# sd1.net
KiCad netlist of a schematic drawn in EAGLE
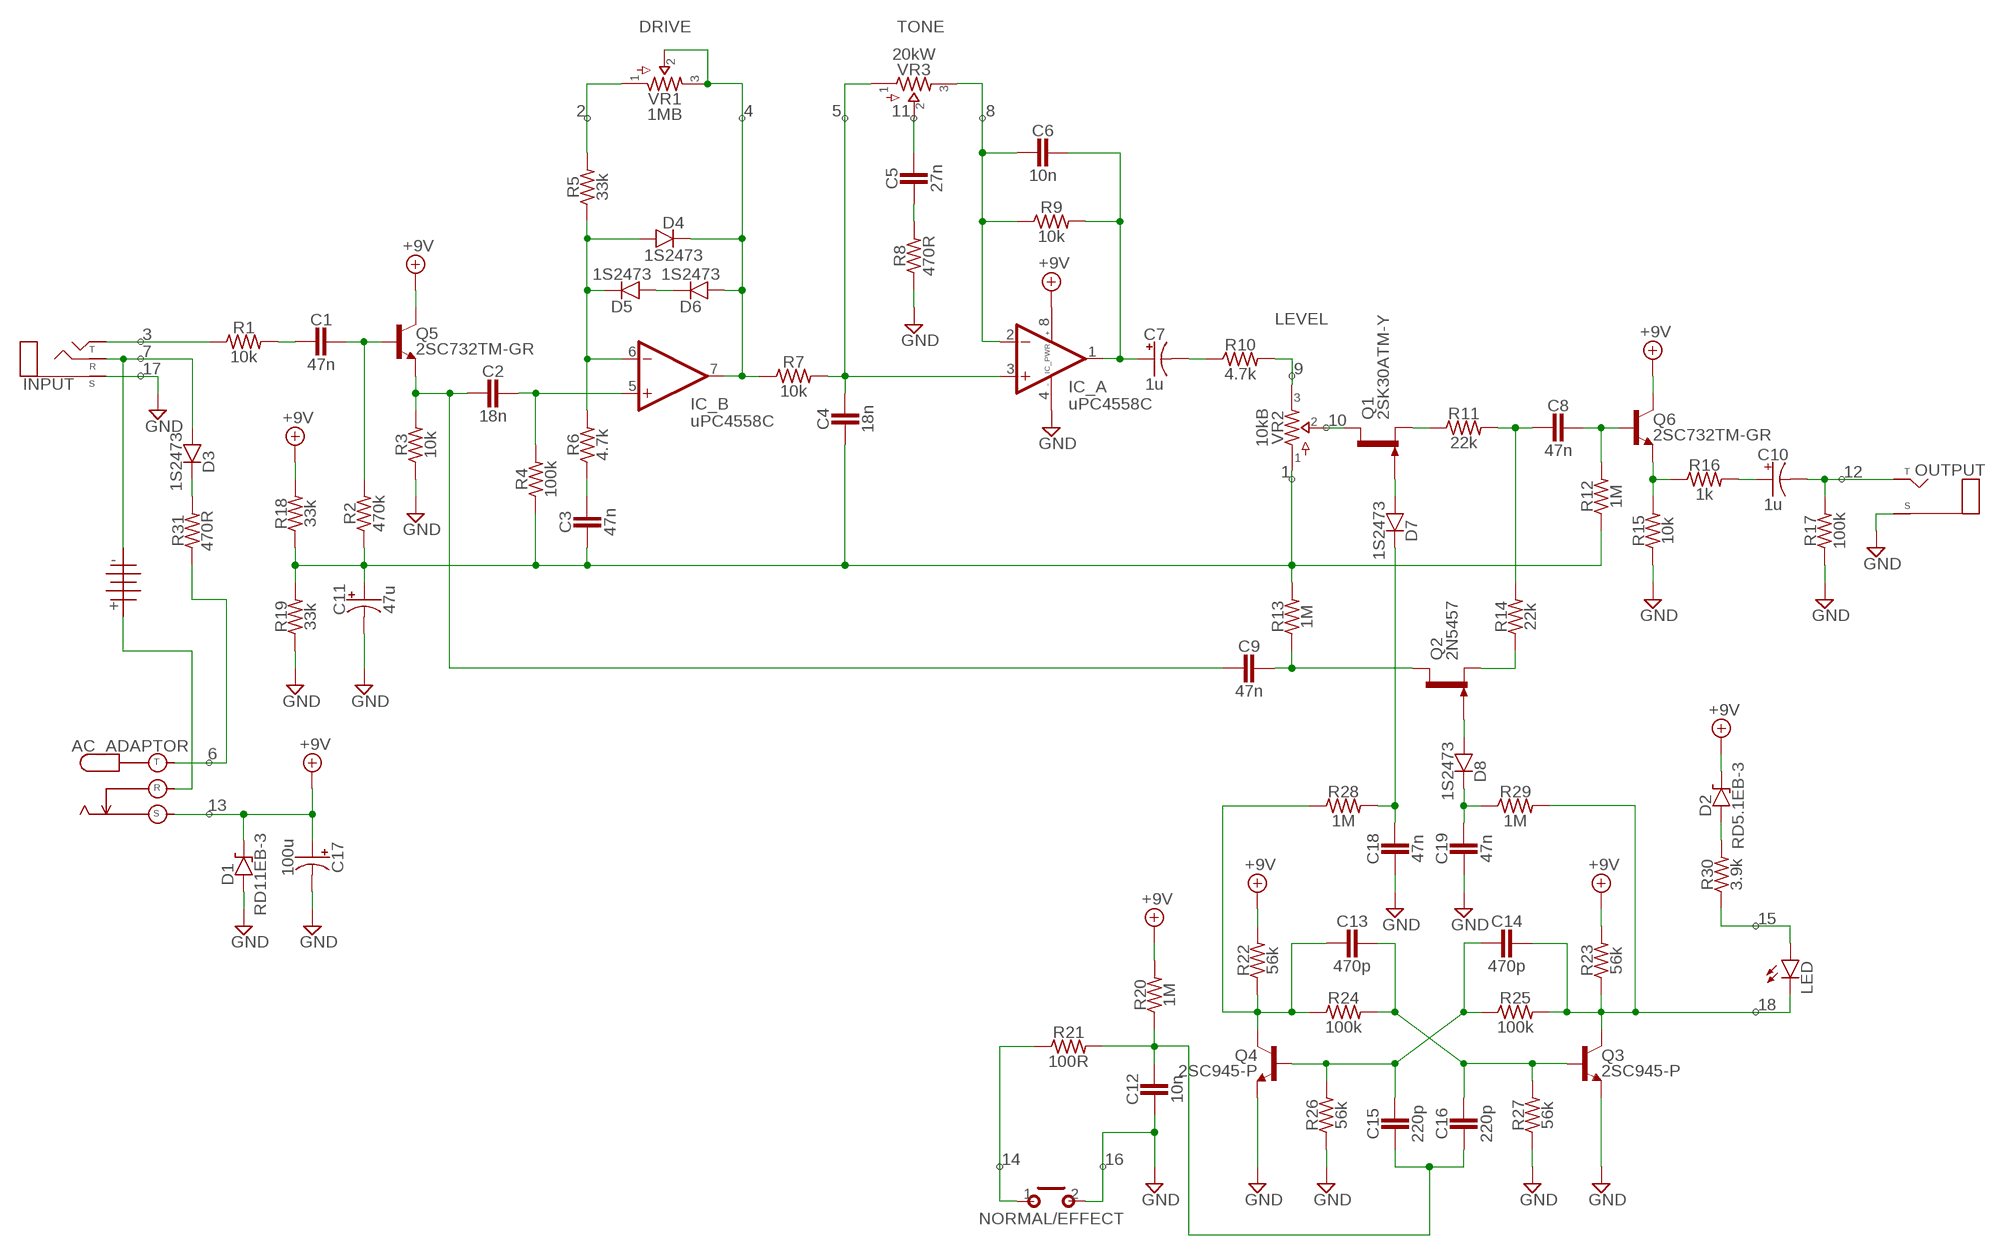
[diagram p0: schematic, sheet 1]

(export (version "E")
  (design (tool "Eeschema 10.0.6"))
  (components
    (comp (ref "AC_ADAPTOR")
      (value "DC_KOBICONN")
      (footprint "eagle-import:DC_KOBICONN")
      (libsource (lib "eagle-import") (part "DC_KOBICONN"))
    )
    (comp (ref "BATTERY")
      (value "BATTERY")
      (footprint "eagle-import:TWO_PADS")
      (libsource (lib "eagle-import") (part "BATTERY"))
    )
    (comp (ref "C1")
      (value "47n")
      (footprint "eagle-import:BOX_SMALL")
      (libsource (lib "eagle-import") (part "CER/FILMBOX.1"))
    )
    (comp (ref "C2")
      (value "18n")
      (footprint "eagle-import:BOX_SMALL")
      (libsource (lib "eagle-import") (part "CER/FILMBOX.1"))
    )
    (comp (ref "C3")
      (value "47n")
      (footprint "eagle-import:BOX_SMALL")
      (libsource (lib "eagle-import") (part "CER/FILMBOX.1"))
    )
    (comp (ref "C4")
      (value "18n")
      (footprint "eagle-import:BOX_SMALL")
      (libsource (lib "eagle-import") (part "CER/FILMBOX.1"))
    )
    (comp (ref "C5")
      (value "27n")
      (footprint "eagle-import:BOX_SMALL")
      (libsource (lib "eagle-import") (part "CER/FILMBOX.1"))
    )
    (comp (ref "C6")
      (value "10n")
      (footprint "eagle-import:BOX_SMALL")
      (libsource (lib "eagle-import") (part "CER/FILMBOX.1"))
    )
    (comp (ref "C7")
      (value "1u")
      (footprint "eagle-import:040_020")
      (libsource (lib "eagle-import") (part "0400"))
    )
    (comp (ref "C8")
      (value "47n")
      (footprint "eagle-import:BOX_SMALL")
      (libsource (lib "eagle-import") (part "CER/FILMBOX.1"))
    )
    (comp (ref "C9")
      (value "47n")
      (footprint "eagle-import:BOX_SMALL")
      (libsource (lib "eagle-import") (part "CER/FILMBOX.1"))
    )
    (comp (ref "C10")
      (value "1u")
      (footprint "eagle-import:040_020")
      (libsource (lib "eagle-import") (part "0400"))
    )
    (comp (ref "C11")
      (value "47u")
      (footprint "eagle-import:040_020")
      (libsource (lib "eagle-import") (part "0400"))
    )
    (comp (ref "C12")
      (value "10n")
      (footprint "eagle-import:BOX_SMALL")
      (libsource (lib "eagle-import") (part "CER/FILMBOX.1"))
    )
    (comp (ref "C13")
      (value "470p")
      (footprint "eagle-import:BOX_SMALL")
      (libsource (lib "eagle-import") (part "CER/FILMBOX.1"))
    )
    (comp (ref "C14")
      (value "470p")
      (footprint "eagle-import:BOX_SMALL")
      (libsource (lib "eagle-import") (part "CER/FILMBOX.1"))
    )
    (comp (ref "C15")
      (value "220p")
      (footprint "eagle-import:BOX_SMALL")
      (libsource (lib "eagle-import") (part "CER/FILMBOX.1"))
    )
    (comp (ref "C16")
      (value "220p")
      (footprint "eagle-import:BOX_SMALL")
      (libsource (lib "eagle-import") (part "CER/FILMBOX.1"))
    )
    (comp (ref "C17")
      (value "100u")
      (footprint "eagle-import:040_020")
      (libsource (lib "eagle-import") (part "0400"))
    )
    (comp (ref "C18")
      (value "47n")
      (footprint "eagle-import:BOX_SMALL")
      (libsource (lib "eagle-import") (part "CER/FILMBOX.1"))
    )
    (comp (ref "C19")
      (value "47n")
      (footprint "eagle-import:BOX_SMALL")
      (libsource (lib "eagle-import") (part "CER/FILMBOX.1"))
    )
    (comp (ref "D1")
      (value "RD11EB-3")
      (footprint "eagle-import:DO41-2")
      (libsource (lib "eagle-import") (part "ZENER.2"))
    )
    (comp (ref "D2")
      (value "RD5.1EB-3")
      (footprint "eagle-import:DO41-2")
      (libsource (lib "eagle-import") (part "ZENER.2"))
    )
    (comp (ref "D3")
      (value "1S2473")
      (footprint "eagle-import:DO35-2")
      (libsource (lib "eagle-import") (part "DO35.2"))
    )
    (comp (ref "D4")
      (value "1S2473")
      (footprint "eagle-import:DO35-2")
      (libsource (lib "eagle-import") (part "DO35.2"))
    )
    (comp (ref "D5")
      (value "1S2473")
      (footprint "eagle-import:DO35-2")
      (libsource (lib "eagle-import") (part "DO35.2"))
    )
    (comp (ref "D6")
      (value "1S2473")
      (footprint "eagle-import:DO35-2")
      (libsource (lib "eagle-import") (part "DO35.2"))
    )
    (comp (ref "D7")
      (value "1S2473")
      (footprint "eagle-import:DO35-2")
      (libsource (lib "eagle-import") (part "DO35.2"))
    )
    (comp (ref "D8")
      (value "1S2473")
      (footprint "eagle-import:DO35-2")
      (libsource (lib "eagle-import") (part "DO35.2"))
    )
    (comp (ref "IC")
      (value "uPC4558C")
      (footprint "eagle-import:DIL0")
      (libsource (lib "eagle-import") (part "DUALTH"))
    )
    (comp (ref "INPUT")
      (value "STEREO3PADS")
      (footprint "eagle-import:THREEPADS")
      (libsource (lib "eagle-import") (part "STEREO3PADS"))
    )
    (comp (ref "LED")
      (value "SLP1358")
      (footprint "eagle-import:3MM_D")
      (libsource (lib "eagle-import") (part "LED"))
    )
    (comp (ref "NORMAL/EFFECT")
      (value "MOMENTARY")
      (footprint "eagle-import:SPST")
      (libsource (lib "eagle-import") (part "MOMENTARY"))
    )
    (comp (ref "OUTPUT")
      (value "MONO")
      (footprint "eagle-import:TWO_PADS")
      (libsource (lib "eagle-import") (part "MONO"))
    )
    (comp (ref "Q1")
      (value "2SK30ATM-Y")
      (footprint "eagle-import:TO92-")
      (libsource (lib "eagle-import") (part "2N5457"))
    )
    (comp (ref "Q2")
      (value "2N5457")
      (footprint "eagle-import:TO92-")
      (libsource (lib "eagle-import") (part "2N5457"))
    )
    (comp (ref "Q3")
      (value "2SC945-P")
      (footprint "eagle-import:TO92-")
      (libsource (lib "eagle-import") (part "2SC828A"))
    )
    (comp (ref "Q4")
      (value "2SC945-P")
      (footprint "eagle-import:TO92-")
      (libsource (lib "eagle-import") (part "2SC828A"))
    )
    (comp (ref "Q5")
      (value "2SC732TM-GR")
      (footprint "eagle-import:TO92-")
      (libsource (lib "eagle-import") (part "2SC828A"))
    )
    (comp (ref "Q6")
      (value "2SC732TM-GR")
      (footprint "eagle-import:TO92-")
      (libsource (lib "eagle-import") (part "2SC828A"))
    )
    (comp (ref "R1")
      (value "10k")
      (footprint "eagle-import:R0207_3")
      (libsource (lib "eagle-import") (part "R_.3B"))
    )
    (comp (ref "R2")
      (value "470k")
      (footprint "eagle-import:R0207_3")
      (libsource (lib "eagle-import") (part "R_.3B"))
    )
    (comp (ref "R3")
      (value "10k")
      (footprint "eagle-import:R0207_3")
      (libsource (lib "eagle-import") (part "R_.3B"))
    )
    (comp (ref "R4")
      (value "100k")
      (footprint "eagle-import:R0207_3")
      (libsource (lib "eagle-import") (part "R_.3B"))
    )
    (comp (ref "R5")
      (value "33k")
      (footprint "eagle-import:R0207_3")
      (libsource (lib "eagle-import") (part "R_.3B"))
    )
    (comp (ref "R6")
      (value "4.7k")
      (footprint "eagle-import:R0207_3")
      (libsource (lib "eagle-import") (part "R_.3B"))
    )
    (comp (ref "R7")
      (value "10k")
      (footprint "eagle-import:R0207_3")
      (libsource (lib "eagle-import") (part "R_.3B"))
    )
    (comp (ref "R8")
      (value "470R")
      (footprint "eagle-import:R0207_3")
      (libsource (lib "eagle-import") (part "R_.3B"))
    )
    (comp (ref "R9")
      (value "10k")
      (footprint "eagle-import:R0207_3")
      (libsource (lib "eagle-import") (part "R_.3B"))
    )
    (comp (ref "R10")
      (value "4.7k")
      (footprint "eagle-import:R0207_3")
      (libsource (lib "eagle-import") (part "R_.3B"))
    )
    (comp (ref "R11")
      (value "22k")
      (footprint "eagle-import:R0207_3")
      (libsource (lib "eagle-import") (part "R_.3B"))
    )
    (comp (ref "R12")
      (value "1M")
      (footprint "eagle-import:R0207_3")
      (libsource (lib "eagle-import") (part "R_.3B"))
    )
    (comp (ref "R13")
      (value "1M")
      (footprint "eagle-import:R0207_3")
      (libsource (lib "eagle-import") (part "R_.3B"))
    )
    (comp (ref "R14")
      (value "22k")
      (footprint "eagle-import:R0207_3")
      (libsource (lib "eagle-import") (part "R_.3B"))
    )
    (comp (ref "R15")
      (value "10k")
      (footprint "eagle-import:R0207_3")
      (libsource (lib "eagle-import") (part "R_.3B"))
    )
    (comp (ref "R16")
      (value "1k")
      (footprint "eagle-import:R0207_3")
      (libsource (lib "eagle-import") (part "R_.3B"))
    )
    (comp (ref "R17")
      (value "100k")
      (footprint "eagle-import:R0207_3")
      (libsource (lib "eagle-import") (part "R_.3B"))
    )
    (comp (ref "R18")
      (value "33k")
      (footprint "eagle-import:R0207_3")
      (libsource (lib "eagle-import") (part "R_.3B"))
    )
    (comp (ref "R19")
      (value "33k")
      (footprint "eagle-import:R0207_3")
      (libsource (lib "eagle-import") (part "R_.3B"))
    )
    (comp (ref "R20")
      (value "1M")
      (footprint "eagle-import:R0207_3")
      (libsource (lib "eagle-import") (part "R_.3B"))
    )
    (comp (ref "R21")
      (value "100R")
      (footprint "eagle-import:R0207_3")
      (libsource (lib "eagle-import") (part "R_.3B"))
    )
    (comp (ref "R22")
      (value "56k")
      (footprint "eagle-import:R0207_3")
      (libsource (lib "eagle-import") (part "R_.3B"))
    )
    (comp (ref "R23")
      (value "56k")
      (footprint "eagle-import:R0207_3")
      (libsource (lib "eagle-import") (part "R_.3B"))
    )
    (comp (ref "R24")
      (value "100k")
      (footprint "eagle-import:R0207_3")
      (libsource (lib "eagle-import") (part "R_.3B"))
    )
    (comp (ref "R25")
      (value "100k")
      (footprint "eagle-import:R0207_3")
      (libsource (lib "eagle-import") (part "R_.3B"))
    )
    (comp (ref "R26")
      (value "56k")
      (footprint "eagle-import:R0207_3")
      (libsource (lib "eagle-import") (part "R_.3B"))
    )
    (comp (ref "R27")
      (value "56k")
      (footprint "eagle-import:R0207_3")
      (libsource (lib "eagle-import") (part "R_.3B"))
    )
    (comp (ref "R28")
      (value "1M")
      (footprint "eagle-import:R0207_3")
      (libsource (lib "eagle-import") (part "R_.3B"))
    )
    (comp (ref "R29")
      (value "1M")
      (footprint "eagle-import:R0207_3")
      (libsource (lib "eagle-import") (part "R_.3B"))
    )
    (comp (ref "R30")
      (value "3.9k")
      (footprint "eagle-import:R0207_3")
      (libsource (lib "eagle-import") (part "R_.3B"))
    )
    (comp (ref "R31")
      (value "470R")
      (footprint "eagle-import:R0207_3")
      (libsource (lib "eagle-import") (part "R_.3B"))
    )
    (comp (ref "VR1")
      (value "1MB")
      (footprint "eagle-import:16MM")
      (libsource (lib "eagle-import") (part "POTS16MM"))
    )
    (comp (ref "VR2")
      (value "10kB")
      (footprint "eagle-import:16MM")
      (libsource (lib "eagle-import") (part "POTS16MM"))
    )
    (comp (ref "VR3")
      (value "20kW")
      (footprint "eagle-import:16MM")
      (libsource (lib "eagle-import") (part "POTS16MM"))
    )
  )
  (nets
    (net (code "1") (name "+9V") (class "Default")
      (node (ref "AC_ADAPTOR") (pin "S") (pinfunction "S_S") (pintype "bidirectional"))
      (node (ref "C17") (pin "+") (pinfunction "+_+") (pintype "passive"))
      (node (ref "D1") (pin "C") (pinfunction "C_C") (pintype "passive"))
      (node (ref "D2") (pin "C") (pinfunction "C_C") (pintype "passive"))
      (node (ref "IC") (pin "8") (pinfunction "V+_8") (pintype "power_in"))
      (node (ref "Q5") (pin "2") (pinfunction "C_2") (pintype "passive"))
      (node (ref "Q6") (pin "2") (pinfunction "C_2") (pintype "passive"))
      (node (ref "R18") (pin "2") (pinfunction "2_2") (pintype "passive"))
      (node (ref "R20") (pin "2") (pinfunction "2_2") (pintype "passive"))
      (node (ref "R22") (pin "2") (pinfunction "2_2") (pintype "passive"))
      (node (ref "R23") (pin "2") (pinfunction "2_2") (pintype "passive"))
    )
    (net (code "2") (name "GND") (class "Default")
      (node (ref "C11") (pin "-") (pinfunction "-_-") (pintype "passive"))
      (node (ref "C12") (pin "2") (pinfunction "2_2") (pintype "passive"))
      (node (ref "C17") (pin "-") (pinfunction "-_-") (pintype "passive"))
      (node (ref "C18") (pin "2") (pinfunction "2_2") (pintype "passive"))
      (node (ref "C19") (pin "2") (pinfunction "2_2") (pintype "passive"))
      (node (ref "D1") (pin "A") (pinfunction "A_A") (pintype "passive"))
      (node (ref "IC") (pin "4") (pinfunction "V-_4") (pintype "power_in"))
      (node (ref "INPUT") (pin "SLEEVE") (pinfunction "S_SLEEVE") (pintype "passive"))
      (node (ref "NORMAL/EFFECT") (pin "2") (pinfunction "S_2") (pintype "passive"))
      (node (ref "OUTPUT") (pin "S") (pinfunction "SLEEVE_S") (pintype "passive"))
      (node (ref "Q3") (pin "3") (pinfunction "E_3") (pintype "passive"))
      (node (ref "Q4") (pin "3") (pinfunction "E_3") (pintype "passive"))
      (node (ref "R15") (pin "1") (pinfunction "1_1") (pintype "passive"))
      (node (ref "R17") (pin "1") (pinfunction "1_1") (pintype "passive"))
      (node (ref "R19") (pin "1") (pinfunction "1_1") (pintype "passive"))
      (node (ref "R26") (pin "1") (pinfunction "1_1") (pintype "passive"))
      (node (ref "R27") (pin "1") (pinfunction "1_1") (pintype "passive"))
      (node (ref "R3") (pin "1") (pinfunction "1_1") (pintype "passive"))
      (node (ref "R8") (pin "1") (pinfunction "1_1") (pintype "passive"))
    )
    (net (code "3") (name "Net-(AC_ADAPTOR-PadT)") (class "Default")
      (node (ref "AC_ADAPTOR") (pin "T") (pinfunction "T_T") (pintype "bidirectional"))
      (node (ref "R31") (pin "1") (pinfunction "1_1") (pintype "passive"))
    )
    (net (code "4") (name "Net-(BATTERY-P$1)") (class "Default")
      (node (ref "AC_ADAPTOR") (pin "R") (pinfunction "R_R") (pintype "bidirectional"))
      (node (ref "BATTERY") (pin "T") (pinfunction "P$1_T") (pintype "bidirectional"))
    )
    (net (code "5") (name "Net-(BATTERY-P$2)") (class "Default")
      (node (ref "BATTERY") (pin "S") (pinfunction "P$2_S") (pintype "bidirectional"))
      (node (ref "D3") (pin "A") (pinfunction "A_A") (pintype "passive"))
      (node (ref "INPUT") (pin "RING") (pinfunction "R_RING") (pintype "passive"))
    )
    (net (code "6") (name "Net-(C1-Pad2)") (class "Default")
      (node (ref "C1") (pin "2") (pinfunction "2_2") (pintype "passive"))
      (node (ref "R1") (pin "2") (pinfunction "2_2") (pintype "passive"))
    )
    (net (code "7") (name "Net-(C3-Pad1)") (class "Default")
      (node (ref "C3") (pin "1") (pinfunction "1_1") (pintype "passive"))
      (node (ref "R6") (pin "1") (pinfunction "1_1") (pintype "passive"))
    )
    (net (code "8") (name "Net-(C5-Pad1)") (class "Default")
      (node (ref "C5") (pin "1") (pinfunction "1_1") (pintype "passive"))
      (node (ref "VR3") (pin "2") (pinfunction "2_2") (pintype "passive"))
    )
    (net (code "9") (name "Net-(C5-Pad2)") (class "Default")
      (node (ref "C5") (pin "2") (pinfunction "2_2") (pintype "passive"))
      (node (ref "R8") (pin "2") (pinfunction "2_2") (pintype "passive"))
    )
    (net (code "10") (name "Net-(C7-Pad-)") (class "Default")
      (node (ref "C7") (pin "-") (pinfunction "-_-") (pintype "passive"))
      (node (ref "R10") (pin "1") (pinfunction "1_1") (pintype "passive"))
    )
    (net (code "11") (name "Net-(C8-Pad2)") (class "Default")
      (node (ref "C8") (pin "2") (pinfunction "2_2") (pintype "passive"))
      (node (ref "R11") (pin "2") (pinfunction "2_2") (pintype "passive"))
      (node (ref "R14") (pin "2") (pinfunction "2_2") (pintype "passive"))
    )
    (net (code "12") (name "Net-(C10-Pad+)") (class "Default")
      (node (ref "C10") (pin "+") (pinfunction "+_+") (pintype "passive"))
      (node (ref "R16") (pin "2") (pinfunction "2_2") (pintype "passive"))
    )
    (net (code "13") (name "Net-(C11-Pad+)") (class "Default")
      (node (ref "C11") (pin "+") (pinfunction "+_+") (pintype "passive"))
      (node (ref "C3") (pin "2") (pinfunction "2_2") (pintype "passive"))
      (node (ref "C4") (pin "2") (pinfunction "2_2") (pintype "passive"))
      (node (ref "R12") (pin "1") (pinfunction "1_1") (pintype "passive"))
      (node (ref "R13") (pin "2") (pinfunction "2_2") (pintype "passive"))
      (node (ref "R18") (pin "1") (pinfunction "1_1") (pintype "passive"))
      (node (ref "R19") (pin "2") (pinfunction "2_2") (pintype "passive"))
      (node (ref "R2") (pin "1") (pinfunction "1_1") (pintype "passive"))
      (node (ref "R4") (pin "1") (pinfunction "1_1") (pintype "passive"))
      (node (ref "VR2") (pin "1") (pinfunction "1_1") (pintype "passive"))
    )
    (net (code "14") (name "Net-(C12-Pad1)") (class "Default")
      (node (ref "C12") (pin "1") (pinfunction "1_1") (pintype "passive"))
      (node (ref "C15") (pin "2") (pinfunction "2_2") (pintype "passive"))
      (node (ref "C16") (pin "2") (pinfunction "2_2") (pintype "passive"))
      (node (ref "R20") (pin "1") (pinfunction "1_1") (pintype "passive"))
      (node (ref "R21") (pin "2") (pinfunction "2_2") (pintype "passive"))
    )
    (net (code "15") (name "Net-(C18-Pad1)") (class "Default")
      (node (ref "C18") (pin "1") (pinfunction "1_1") (pintype "passive"))
      (node (ref "D7") (pin "C") (pinfunction "C_C") (pintype "passive"))
      (node (ref "R28") (pin "2") (pinfunction "2_2") (pintype "passive"))
    )
    (net (code "16") (name "Net-(C19-Pad1)") (class "Default")
      (node (ref "C19") (pin "1") (pinfunction "1_1") (pintype "passive"))
      (node (ref "D8") (pin "C") (pinfunction "C_C") (pintype "passive"))
      (node (ref "R29") (pin "1") (pinfunction "1_1") (pintype "passive"))
    )
    (net (code "17") (name "Net-(D2-PadA)") (class "Default")
      (node (ref "D2") (pin "A") (pinfunction "A_A") (pintype "passive"))
      (node (ref "R30") (pin "2") (pinfunction "2_2") (pintype "passive"))
    )
    (net (code "18") (name "Net-(D3-PadC)") (class "Default")
      (node (ref "D3") (pin "C") (pinfunction "C_C") (pintype "passive"))
      (node (ref "R31") (pin "2") (pinfunction "2_2") (pintype "passive"))
    )
    (net (code "19") (name "Net-(D5-PadA)") (class "Default")
      (node (ref "D5") (pin "A") (pinfunction "A_A") (pintype "passive"))
      (node (ref "D6") (pin "C") (pinfunction "C_C") (pintype "passive"))
    )
    (net (code "20") (name "Net-(ICA-+IN)") (class "Default")
      (node (ref "C4") (pin "1") (pinfunction "1_1") (pintype "passive"))
      (node (ref "IC") (pin "3") (pinfunction "+IN_3") (pintype "input"))
      (node (ref "R7") (pin "2") (pinfunction "2_2") (pintype "passive"))
      (node (ref "VR3") (pin "1") (pinfunction "1_1") (pintype "passive"))
    )
    (net (code "21") (name "Net-(ICA--IN)") (class "Default")
      (node (ref "C6") (pin "2") (pinfunction "2_2") (pintype "passive"))
      (node (ref "IC") (pin "2") (pinfunction "-IN_2") (pintype "input"))
      (node (ref "R9") (pin "1") (pinfunction "1_1") (pintype "passive"))
      (node (ref "VR3") (pin "3") (pinfunction "3_3") (pintype "passive"))
    )
    (net (code "22") (name "Net-(ICA-OUT)") (class "Default")
      (node (ref "C6") (pin "1") (pinfunction "1_1") (pintype "passive"))
      (node (ref "C7") (pin "+") (pinfunction "+_+") (pintype "passive"))
      (node (ref "IC") (pin "1") (pinfunction "OUT_1") (pintype "output"))
      (node (ref "R9") (pin "2") (pinfunction "2_2") (pintype "passive"))
    )
    (net (code "23") (name "Net-(ICB-+IN)") (class "Default")
      (node (ref "C2") (pin "1") (pinfunction "1_1") (pintype "passive"))
      (node (ref "IC") (pin "5") (pinfunction "+IN_5") (pintype "input"))
      (node (ref "R4") (pin "2") (pinfunction "2_2") (pintype "passive"))
    )
    (net (code "24") (name "Net-(ICB--IN)") (class "Default")
      (node (ref "D4") (pin "A") (pinfunction "A_A") (pintype "passive"))
      (node (ref "D5") (pin "C") (pinfunction "C_C") (pintype "passive"))
      (node (ref "IC") (pin "6") (pinfunction "-IN_6") (pintype "input"))
      (node (ref "R5") (pin "1") (pinfunction "1_1") (pintype "passive"))
      (node (ref "R6") (pin "2") (pinfunction "2_2") (pintype "passive"))
    )
    (net (code "25") (name "Net-(ICB-OUT)") (class "Default")
      (node (ref "D4") (pin "C") (pinfunction "C_C") (pintype "passive"))
      (node (ref "D6") (pin "A") (pinfunction "A_A") (pintype "passive"))
      (node (ref "IC") (pin "7") (pinfunction "OUT_7") (pintype "output"))
      (node (ref "R7") (pin "1") (pinfunction "1_1") (pintype "passive"))
      (node (ref "VR1") (pin "2") (pinfunction "2_2") (pintype "passive"))
      (node (ref "VR1") (pin "3") (pinfunction "3_3") (pintype "passive"))
    )
    (net (code "26") (name "Net-(INPUT-T)") (class "Default")
      (node (ref "INPUT") (pin "TIP") (pinfunction "T_TIP") (pintype "passive"))
      (node (ref "R1") (pin "1") (pinfunction "1_1") (pintype "passive"))
    )
    (net (code "27") (name "Net-(LED-A)") (class "Default")
      (node (ref "LED") (pin "ANODE") (pinfunction "A_ANODE") (pintype "passive"))
      (node (ref "R30") (pin "1") (pinfunction "1_1") (pintype "passive"))
    )
    (net (code "28") (name "Net-(LED-C)") (class "Default")
      (node (ref "C14") (pin "1") (pinfunction "1_1") (pintype "passive"))
      (node (ref "LED") (pin "P$1") (pinfunction "C_P$1") (pintype "passive"))
      (node (ref "Q3") (pin "2") (pinfunction "C_2") (pintype "passive"))
      (node (ref "R23") (pin "1") (pinfunction "1_1") (pintype "passive"))
      (node (ref "R25") (pin "2") (pinfunction "2_2") (pintype "passive"))
      (node (ref "R29") (pin "2") (pinfunction "2_2") (pintype "passive"))
    )
    (net (code "29") (name "Net-(NORMAL/EFFECT-P)") (class "Default")
      (node (ref "NORMAL/EFFECT") (pin "1") (pinfunction "P_1") (pintype "passive"))
      (node (ref "R21") (pin "1") (pinfunction "1_1") (pintype "passive"))
    )
    (net (code "30") (name "Net-(OUTPUT-TIP)") (class "Default")
      (node (ref "C10") (pin "-") (pinfunction "-_-") (pintype "passive"))
      (node (ref "OUTPUT") (pin "T") (pinfunction "TIP_T") (pintype "passive"))
      (node (ref "R17") (pin "2") (pinfunction "2_2") (pintype "passive"))
    )
    (net (code "31") (name "Net-(Q1-D)") (class "Default")
      (node (ref "Q1") (pin "3") (pinfunction "D_3") (pintype "passive"))
      (node (ref "VR2") (pin "2") (pinfunction "2_2") (pintype "passive"))
    )
    (net (code "32") (name "Net-(Q1-G)") (class "Default")
      (node (ref "D7") (pin "A") (pinfunction "A_A") (pintype "passive"))
      (node (ref "Q1") (pin "1") (pinfunction "G_1") (pintype "passive"))
    )
    (net (code "33") (name "Net-(Q1-S)") (class "Default")
      (node (ref "Q1") (pin "2") (pinfunction "S_2") (pintype "passive"))
      (node (ref "R11") (pin "1") (pinfunction "1_1") (pintype "passive"))
    )
    (net (code "34") (name "Net-(Q2-D)") (class "Default")
      (node (ref "C9") (pin "1") (pinfunction "1_1") (pintype "passive"))
      (node (ref "Q2") (pin "3") (pinfunction "D_3") (pintype "passive"))
      (node (ref "R13") (pin "1") (pinfunction "1_1") (pintype "passive"))
    )
    (net (code "35") (name "Net-(Q2-G)") (class "Default")
      (node (ref "D8") (pin "A") (pinfunction "A_A") (pintype "passive"))
      (node (ref "Q2") (pin "1") (pinfunction "G_1") (pintype "passive"))
    )
    (net (code "36") (name "Net-(Q2-S)") (class "Default")
      (node (ref "Q2") (pin "2") (pinfunction "S_2") (pintype "passive"))
      (node (ref "R14") (pin "1") (pinfunction "1_1") (pintype "passive"))
    )
    (net (code "37") (name "Net-(Q3-B)") (class "Default")
      (node (ref "C13") (pin "1") (pinfunction "1_1") (pintype "passive"))
      (node (ref "C16") (pin "1") (pinfunction "1_1") (pintype "passive"))
      (node (ref "Q3") (pin "1") (pinfunction "B_1") (pintype "passive"))
      (node (ref "R24") (pin "2") (pinfunction "2_2") (pintype "passive"))
      (node (ref "R27") (pin "2") (pinfunction "2_2") (pintype "passive"))
    )
    (net (code "38") (name "Net-(Q4-B)") (class "Default")
      (node (ref "C14") (pin "2") (pinfunction "2_2") (pintype "passive"))
      (node (ref "C15") (pin "1") (pinfunction "1_1") (pintype "passive"))
      (node (ref "Q4") (pin "1") (pinfunction "B_1") (pintype "passive"))
      (node (ref "R25") (pin "1") (pinfunction "1_1") (pintype "passive"))
      (node (ref "R26") (pin "2") (pinfunction "2_2") (pintype "passive"))
    )
    (net (code "39") (name "Net-(Q4-C)") (class "Default")
      (node (ref "C13") (pin "2") (pinfunction "2_2") (pintype "passive"))
      (node (ref "Q4") (pin "2") (pinfunction "C_2") (pintype "passive"))
      (node (ref "R22") (pin "1") (pinfunction "1_1") (pintype "passive"))
      (node (ref "R24") (pin "1") (pinfunction "1_1") (pintype "passive"))
      (node (ref "R28") (pin "1") (pinfunction "1_1") (pintype "passive"))
    )
    (net (code "40") (name "Net-(Q5-B)") (class "Default")
      (node (ref "C1") (pin "1") (pinfunction "1_1") (pintype "passive"))
      (node (ref "Q5") (pin "1") (pinfunction "B_1") (pintype "passive"))
      (node (ref "R2") (pin "2") (pinfunction "2_2") (pintype "passive"))
    )
    (net (code "41") (name "Net-(Q5-E)") (class "Default")
      (node (ref "C2") (pin "2") (pinfunction "2_2") (pintype "passive"))
      (node (ref "C9") (pin "2") (pinfunction "2_2") (pintype "passive"))
      (node (ref "Q5") (pin "3") (pinfunction "E_3") (pintype "passive"))
      (node (ref "R3") (pin "2") (pinfunction "2_2") (pintype "passive"))
    )
    (net (code "42") (name "Net-(Q6-B)") (class "Default")
      (node (ref "C8") (pin "1") (pinfunction "1_1") (pintype "passive"))
      (node (ref "Q6") (pin "1") (pinfunction "B_1") (pintype "passive"))
      (node (ref "R12") (pin "2") (pinfunction "2_2") (pintype "passive"))
    )
    (net (code "43") (name "Net-(Q6-E)") (class "Default")
      (node (ref "Q6") (pin "3") (pinfunction "E_3") (pintype "passive"))
      (node (ref "R15") (pin "2") (pinfunction "2_2") (pintype "passive"))
      (node (ref "R16") (pin "1") (pinfunction "1_1") (pintype "passive"))
    )
    (net (code "44") (name "Net-(R5-Pad2)") (class "Default")
      (node (ref "R5") (pin "2") (pinfunction "2_2") (pintype "passive"))
      (node (ref "VR1") (pin "1") (pinfunction "1_1") (pintype "passive"))
    )
    (net (code "45") (name "Net-(R10-Pad2)") (class "Default")
      (node (ref "R10") (pin "2") (pinfunction "2_2") (pintype "passive"))
      (node (ref "VR2") (pin "3") (pinfunction "3_3") (pintype "passive"))
    )
  )
)
